# modicum.net
KiCad netlist of a schematic drawn in EAGLE
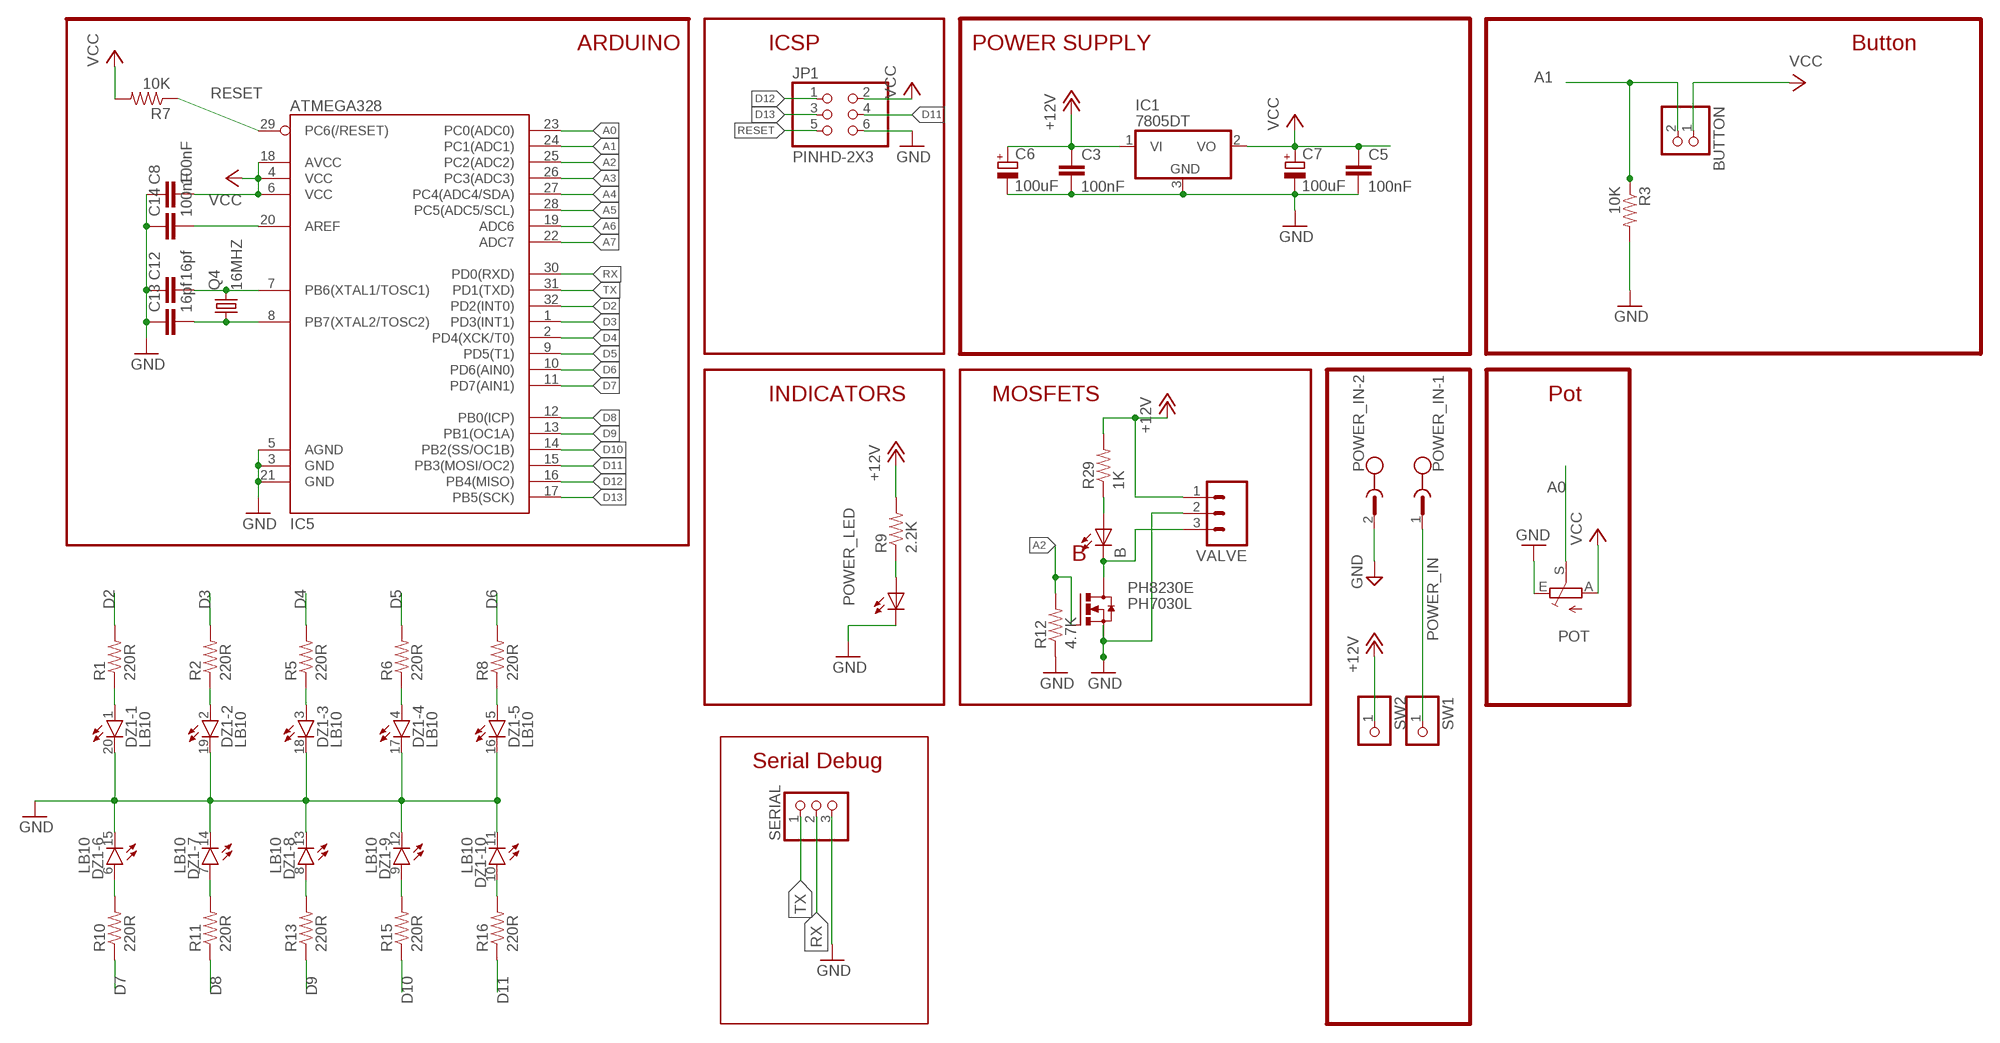
[diagram p0: schematic, sheet 1]

(export (version "E")
  (design (tool "Eeschema 10.0.6"))
  (components
    (comp (ref "B")
      (value "LED0805")
      (footprint "eagle-import:LED-0805")
      (libsource (lib "eagle-import") (part "LED0805"))
    )
    (comp (ref "BUTTON")
      (value "PINHD-1X2")
      (footprint "eagle-import:1X02")
      (libsource (lib "eagle-import") (part "PINHD-1X2"))
    )
    (comp (ref "C3")
      (value "100nF")
      (footprint "eagle-import:0805")
      (libsource (lib "eagle-import") (part "CAP0805"))
    )
    (comp (ref "C5")
      (value "100nF")
      (footprint "eagle-import:0805")
      (libsource (lib "eagle-import") (part "CAP0805"))
    )
    (comp (ref "C6")
      (value "100uF")
      (footprint "eagle-import:E3,5-8")
      (libsource (lib "eagle-import") (part "CPOL-EUE3.5-8"))
    )
    (comp (ref "C7")
      (value "100uF")
      (footprint "eagle-import:E3,5-8")
      (libsource (lib "eagle-import") (part "CPOL-EUE3.5-8"))
    )
    (comp (ref "C8")
      (value "100nF")
      (footprint "eagle-import:0805")
      (libsource (lib "eagle-import") (part "CAP0805"))
    )
    (comp (ref "C12")
      (value "16pf")
      (footprint "eagle-import:0805")
      (libsource (lib "eagle-import") (part "CAP0805"))
    )
    (comp (ref "C13")
      (value "16pf")
      (footprint "eagle-import:0805")
      (libsource (lib "eagle-import") (part "CAP0805"))
    )
    (comp (ref "C14")
      (value "100nF")
      (footprint "eagle-import:0805")
      (libsource (lib "eagle-import") (part "CAP0805"))
    )
    (comp (ref "DZ1")
      (value "LB10")
      (footprint "eagle-import:LB10")
      (libsource (lib "eagle-import") (part "LB10"))
    )
    (comp (ref "IC1")
      (value "7805DT")
      (footprint "eagle-import:TO252")
      (libsource (lib "eagle-import") (part "78DT05"))
    )
    (comp (ref "IC5")
      (value "ATMEGA328")
      (footprint "eagle-import:TQFP32-08")
      (libsource (lib "eagle-import") (part "ATMEGA168"))
    )
    (comp (ref "JP1")
      (value "PINHD-2X3")
      (footprint "eagle-import:2X03")
      (libsource (lib "eagle-import") (part "PINHD-2X3"))
    )
    (comp (ref "PH8230E")
      (value "PH7030L")
      (footprint "eagle-import:SOT669")
      (libsource (lib "eagle-import") (part "PH7030L"))
    )
    (comp (ref "POT")
      (value "TRIM_EU-CIP20C-6MM")
      (footprint "eagle-import:CIP20C-6MM")
      (libsource (lib "eagle-import") (part "TRIM_EU-CIP20C-6MM"))
    )
    (comp (ref "POWER_IN")
      (value "MST2V")
      (footprint "eagle-import:MSTBV2")
      (libsource (lib "eagle-import") (part "MST2V"))
    )
    (comp (ref "POWER_LED")
      (value "LED0805")
      (footprint "eagle-import:LED-0805")
      (libsource (lib "eagle-import") (part "LED0805"))
    )
    (comp (ref "Q4")
      (value "16MHZ")
      (footprint "eagle-import:HC49_S")
      (libsource (lib "eagle-import") (part "CRYSTALHC49S"))
    )
    (comp (ref "R1")
      (value "220R")
      (footprint "eagle-import:0805")
      (libsource (lib "eagle-import") (part "RESISTOR"))
    )
    (comp (ref "R2")
      (value "220R")
      (footprint "eagle-import:0805")
      (libsource (lib "eagle-import") (part "RESISTOR"))
    )
    (comp (ref "R3")
      (value "10K")
      (footprint "eagle-import:0805")
      (libsource (lib "eagle-import") (part "RESISTOR"))
    )
    (comp (ref "R5")
      (value "220R")
      (footprint "eagle-import:0805")
      (libsource (lib "eagle-import") (part "RESISTOR"))
    )
    (comp (ref "R6")
      (value "220R")
      (footprint "eagle-import:0805")
      (libsource (lib "eagle-import") (part "RESISTOR"))
    )
    (comp (ref "R7")
      (value "10K")
      (footprint "eagle-import:0805")
      (libsource (lib "eagle-import") (part "RESISTOR"))
    )
    (comp (ref "R8")
      (value "220R")
      (footprint "eagle-import:0805")
      (libsource (lib "eagle-import") (part "RESISTOR"))
    )
    (comp (ref "R9")
      (value "2.2K")
      (footprint "eagle-import:0805")
      (libsource (lib "eagle-import") (part "RESISTOR"))
    )
    (comp (ref "R10")
      (value "220R")
      (footprint "eagle-import:0805")
      (libsource (lib "eagle-import") (part "RESISTOR"))
    )
    (comp (ref "R11")
      (value "220R")
      (footprint "eagle-import:0805")
      (libsource (lib "eagle-import") (part "RESISTOR"))
    )
    (comp (ref "R12")
      (value "4.7K")
      (footprint "eagle-import:0805")
      (libsource (lib "eagle-import") (part "RESISTOR"))
    )
    (comp (ref "R13")
      (value "220R")
      (footprint "eagle-import:0805")
      (libsource (lib "eagle-import") (part "RESISTOR"))
    )
    (comp (ref "R15")
      (value "220R")
      (footprint "eagle-import:0805")
      (libsource (lib "eagle-import") (part "RESISTOR"))
    )
    (comp (ref "R16")
      (value "220R")
      (footprint "eagle-import:0805")
      (libsource (lib "eagle-import") (part "RESISTOR"))
    )
    (comp (ref "R29")
      (value "1K")
      (footprint "eagle-import:0805")
      (libsource (lib "eagle-import") (part "RESISTOR"))
    )
    (comp (ref "SERIAL")
      (value "PINHD-1X3")
      (footprint "eagle-import:1X03")
      (libsource (lib "eagle-import") (part "PINHD-1X3"))
    )
    (comp (ref "SW1")
      (value "PINHD-1X1")
      (footprint "eagle-import:1X01")
      (libsource (lib "eagle-import") (part "PINHD-1X1"))
    )
    (comp (ref "SW2")
      (value "PINHD-1X1")
      (footprint "eagle-import:1X01")
      (libsource (lib "eagle-import") (part "PINHD-1X1"))
    )
    (comp (ref "VALVE")
      (value "M03")
      (footprint "eagle-import:03P")
      (libsource (lib "eagle-import") (part "M03"))
    )
  )
  (nets
    (net (code "1") (name "+12V") (class "Default")
      (node (ref "C3") (pin "1") (pinfunction "1_1") (pintype "passive"))
      (node (ref "C6") (pin "+") (pinfunction "+_+") (pintype "passive"))
      (node (ref "IC1") (pin "1") (pinfunction "VI_1") (pintype "input"))
      (node (ref "R29") (pin "2") (pinfunction "2_2") (pintype "passive"))
      (node (ref "R9") (pin "2") (pinfunction "2_2") (pintype "passive"))
      (node (ref "SW2") (pin "1") (pinfunction "1_1") (pintype "passive"))
      (node (ref "VALVE") (pin "1") (pinfunction "1_1") (pintype "passive"))
    )
    (net (code "2") (name "/POWER_IN") (class "Default")
      (node (ref "POWER_IN") (pin "1") (pinfunction "1_1") (pintype "passive"))
      (node (ref "SW1") (pin "1") (pinfunction "1_1") (pintype "passive"))
    )
    (net (code "3") (name "A0") (class "Default")
      (node (ref "IC5") (pin "23") (pinfunction "PC0(ADC0)_23") (pintype "bidirectional"))
      (node (ref "POT") (pin "S") (pinfunction "S_S") (pintype "passive"))
    )
    (net (code "4") (name "A1") (class "Default")
      (node (ref "BUTTON") (pin "2") (pinfunction "2_2") (pintype "passive"))
      (node (ref "IC5") (pin "24") (pinfunction "PC1(ADC1)_24") (pintype "bidirectional"))
      (node (ref "R3") (pin "1") (pinfunction "1_1") (pintype "passive"))
    )
    (net (code "5") (name "A2") (class "Default")
      (node (ref "IC5") (pin "25") (pinfunction "PC2(ADC2)_25") (pintype "bidirectional"))
      (node (ref "PH8230E") (pin "4") (pinfunction "G_4") (pintype "passive"))
      (node (ref "R12") (pin "2") (pinfunction "2_2") (pintype "passive"))
    )
    (net (code "6") (name "A3") (class "Default")
      (node (ref "IC5") (pin "26") (pinfunction "PC3(ADC3)_26") (pintype "bidirectional"))
    )
    (net (code "7") (name "A4") (class "Default")
      (node (ref "IC5") (pin "27") (pinfunction "PC4(ADC4/SDA)_27") (pintype "bidirectional"))
    )
    (net (code "8") (name "A5") (class "Default")
      (node (ref "IC5") (pin "28") (pinfunction "PC5(ADC5/SCL)_28") (pintype "bidirectional"))
    )
    (net (code "9") (name "A6") (class "Default")
      (node (ref "IC5") (pin "19") (pinfunction "ADC6_19") (pintype "bidirectional"))
    )
    (net (code "10") (name "A7") (class "Default")
      (node (ref "IC5") (pin "22") (pinfunction "ADC7_22") (pintype "bidirectional"))
    )
    (net (code "11") (name "D2") (class "Default")
      (node (ref "IC5") (pin "32") (pinfunction "PD2(INT0)_32") (pintype "bidirectional"))
      (node (ref "R1") (pin "2") (pinfunction "2_2") (pintype "passive"))
    )
    (net (code "12") (name "D3") (class "Default")
      (node (ref "IC5") (pin "1") (pinfunction "PD3(INT1)_1") (pintype "bidirectional"))
      (node (ref "R2") (pin "2") (pinfunction "2_2") (pintype "passive"))
    )
    (net (code "13") (name "D4") (class "Default")
      (node (ref "IC5") (pin "2") (pinfunction "PD4(XCK/T0)_2") (pintype "bidirectional"))
      (node (ref "R5") (pin "2") (pinfunction "2_2") (pintype "passive"))
    )
    (net (code "14") (name "D5") (class "Default")
      (node (ref "IC5") (pin "9") (pinfunction "PD5(T1)_9") (pintype "bidirectional"))
      (node (ref "R6") (pin "2") (pinfunction "2_2") (pintype "passive"))
    )
    (net (code "15") (name "D6") (class "Default")
      (node (ref "IC5") (pin "10") (pinfunction "PD6(AIN0)_10") (pintype "bidirectional"))
      (node (ref "R8") (pin "2") (pinfunction "2_2") (pintype "passive"))
    )
    (net (code "16") (name "D7") (class "Default")
      (node (ref "IC5") (pin "11") (pinfunction "PD7(AIN1)_11") (pintype "bidirectional"))
      (node (ref "R10") (pin "1") (pinfunction "1_1") (pintype "passive"))
    )
    (net (code "17") (name "D8") (class "Default")
      (node (ref "IC5") (pin "12") (pinfunction "PB0(ICP)_12") (pintype "bidirectional"))
      (node (ref "R11") (pin "1") (pinfunction "1_1") (pintype "passive"))
    )
    (net (code "18") (name "D9") (class "Default")
      (node (ref "IC5") (pin "13") (pinfunction "PB1(OC1A)_13") (pintype "bidirectional"))
      (node (ref "R13") (pin "1") (pinfunction "1_1") (pintype "passive"))
    )
    (net (code "19") (name "D10") (class "Default")
      (node (ref "IC5") (pin "14") (pinfunction "PB2(SS/OC1B)_14") (pintype "bidirectional"))
      (node (ref "R15") (pin "1") (pinfunction "1_1") (pintype "passive"))
    )
    (net (code "20") (name "D11") (class "Default")
      (node (ref "IC5") (pin "15") (pinfunction "PB3(MOSI/OC2)_15") (pintype "bidirectional"))
      (node (ref "JP1") (pin "4") (pinfunction "4_4") (pintype "passive"))
      (node (ref "R16") (pin "1") (pinfunction "1_1") (pintype "passive"))
    )
    (net (code "21") (name "D12") (class "Default")
      (node (ref "IC5") (pin "16") (pinfunction "PB4(MISO)_16") (pintype "bidirectional"))
      (node (ref "JP1") (pin "1") (pinfunction "1_1") (pintype "passive"))
    )
    (net (code "22") (name "D13") (class "Default")
      (node (ref "IC5") (pin "17") (pinfunction "PB5(SCK)_17") (pintype "bidirectional"))
      (node (ref "JP1") (pin "3") (pinfunction "3_3") (pintype "passive"))
    )
    (net (code "23") (name "GND") (class "Default")
      (node (ref "C12") (pin "1") (pinfunction "1_1") (pintype "passive"))
      (node (ref "C13") (pin "1") (pinfunction "1_1") (pintype "passive"))
      (node (ref "C14") (pin "1") (pinfunction "1_1") (pintype "passive"))
      (node (ref "C3") (pin "2") (pinfunction "2_2") (pintype "passive"))
      (node (ref "C5") (pin "2") (pinfunction "2_2") (pintype "passive"))
      (node (ref "C6") (pin "-") (pinfunction "-_-") (pintype "passive"))
      (node (ref "C7") (pin "-") (pinfunction "-_-") (pintype "passive"))
      (node (ref "C8") (pin "1") (pinfunction "1_1") (pintype "passive"))
      (node (ref "DZ1") (pin "11") (pinfunction "C_11") (pintype "passive"))
      (node (ref "DZ1") (pin "12") (pinfunction "C_12") (pintype "passive"))
      (node (ref "DZ1") (pin "13") (pinfunction "C_13") (pintype "passive"))
      (node (ref "DZ1") (pin "14") (pinfunction "C_14") (pintype "passive"))
      (node (ref "DZ1") (pin "15") (pinfunction "C_15") (pintype "passive"))
      (node (ref "DZ1") (pin "16") (pinfunction "C_16") (pintype "passive"))
      (node (ref "DZ1") (pin "17") (pinfunction "C_17") (pintype "passive"))
      (node (ref "DZ1") (pin "18") (pinfunction "C_18") (pintype "passive"))
      (node (ref "DZ1") (pin "19") (pinfunction "C_19") (pintype "passive"))
      (node (ref "DZ1") (pin "20") (pinfunction "C_20") (pintype "passive"))
      (node (ref "IC1") (pin "3") (pinfunction "GND_3") (pintype "passive"))
      (node (ref "IC5") (pin "21") (pinfunction "GND_21") (pintype "bidirectional"))
      (node (ref "IC5") (pin "3") (pinfunction "GND_3") (pintype "bidirectional"))
      (node (ref "IC5") (pin "5") (pinfunction "AGND_5") (pintype "bidirectional"))
      (node (ref "JP1") (pin "6") (pinfunction "6_6") (pintype "passive"))
      (node (ref "PH8230E") (pin "1") (pinfunction "S_1") (pintype "passive"))
      (node (ref "PH8230E") (pin "2") (pinfunction "S_2") (pintype "passive"))
      (node (ref "PH8230E") (pin "3") (pinfunction "S_3") (pintype "passive"))
      (node (ref "POT") (pin "E") (pinfunction "E_E") (pintype "passive"))
      (node (ref "POWER_IN") (pin "2") (pinfunction "1_2") (pintype "passive"))
      (node (ref "POWER_LED") (pin "C") (pinfunction "C_C") (pintype "passive"))
      (node (ref "R12") (pin "1") (pinfunction "1_1") (pintype "passive"))
      (node (ref "R3") (pin "2") (pinfunction "2_2") (pintype "passive"))
      (node (ref "SERIAL") (pin "3") (pinfunction "3_3") (pintype "passive"))
      (node (ref "VALVE") (pin "2") (pinfunction "2_2") (pintype "passive"))
    )
    (net (code "24") (name "Net-(B-PadA)") (class "Default")
      (node (ref "B") (pin "A") (pinfunction "A_A") (pintype "passive"))
      (node (ref "R29") (pin "1") (pinfunction "1_1") (pintype "passive"))
    )
    (net (code "25") (name "Net-(DZ1A-A)") (class "Default")
      (node (ref "DZ1") (pin "1") (pinfunction "A_1") (pintype "passive"))
      (node (ref "R1") (pin "1") (pinfunction "1_1") (pintype "passive"))
    )
    (net (code "26") (name "Net-(DZ1B-A)") (class "Default")
      (node (ref "DZ1") (pin "10") (pinfunction "A_10") (pintype "passive"))
      (node (ref "R16") (pin "2") (pinfunction "2_2") (pintype "passive"))
    )
    (net (code "27") (name "Net-(DZ1C-A)") (class "Default")
      (node (ref "DZ1") (pin "2") (pinfunction "A_2") (pintype "passive"))
      (node (ref "R2") (pin "1") (pinfunction "1_1") (pintype "passive"))
    )
    (net (code "28") (name "Net-(DZ1D-A)") (class "Default")
      (node (ref "DZ1") (pin "3") (pinfunction "A_3") (pintype "passive"))
      (node (ref "R5") (pin "1") (pinfunction "1_1") (pintype "passive"))
    )
    (net (code "29") (name "Net-(DZ1E-A)") (class "Default")
      (node (ref "DZ1") (pin "4") (pinfunction "A_4") (pintype "passive"))
      (node (ref "R6") (pin "1") (pinfunction "1_1") (pintype "passive"))
    )
    (net (code "30") (name "Net-(DZ1F-A)") (class "Default")
      (node (ref "DZ1") (pin "5") (pinfunction "A_5") (pintype "passive"))
      (node (ref "R8") (pin "1") (pinfunction "1_1") (pintype "passive"))
    )
    (net (code "31") (name "Net-(DZ1G-A)") (class "Default")
      (node (ref "DZ1") (pin "6") (pinfunction "A_6") (pintype "passive"))
      (node (ref "R10") (pin "2") (pinfunction "2_2") (pintype "passive"))
    )
    (net (code "32") (name "Net-(DZ1H-A)") (class "Default")
      (node (ref "DZ1") (pin "7") (pinfunction "A_7") (pintype "passive"))
      (node (ref "R11") (pin "2") (pinfunction "2_2") (pintype "passive"))
    )
    (net (code "33") (name "Net-(DZ1I-A)") (class "Default")
      (node (ref "DZ1") (pin "8") (pinfunction "A_8") (pintype "passive"))
      (node (ref "R13") (pin "2") (pinfunction "2_2") (pintype "passive"))
    )
    (net (code "34") (name "Net-(DZ1J-A)") (class "Default")
      (node (ref "DZ1") (pin "9") (pinfunction "A_9") (pintype "passive"))
      (node (ref "R15") (pin "2") (pinfunction "2_2") (pintype "passive"))
    )
    (net (code "35") (name "Net-(IC5-AREF)") (class "Default")
      (node (ref "C14") (pin "2") (pinfunction "2_2") (pintype "passive"))
      (node (ref "IC5") (pin "20") (pinfunction "AREF_20") (pintype "bidirectional"))
    )
    (net (code "36") (name "Net-(IC5-PB6(XTAL1{slash}TOSC1))") (class "Default")
      (node (ref "C12") (pin "2") (pinfunction "2_2") (pintype "passive"))
      (node (ref "IC5") (pin "7") (pinfunction "PB6(XTAL1/TOSC1)_7") (pintype "bidirectional"))
      (node (ref "Q4") (pin "2") (pinfunction "2_2") (pintype "passive"))
    )
    (net (code "37") (name "Net-(IC5-PB7(XTAL2{slash}TOSC2))") (class "Default")
      (node (ref "C13") (pin "2") (pinfunction "2_2") (pintype "passive"))
      (node (ref "IC5") (pin "8") (pinfunction "PB7(XTAL2/TOSC2)_8") (pintype "bidirectional"))
      (node (ref "Q4") (pin "1") (pinfunction "1_1") (pintype "passive"))
    )
    (net (code "38") (name "Net-(PH8230E-D)") (class "Default")
      (node (ref "B") (pin "C") (pinfunction "C_C") (pintype "passive"))
      (node (ref "PH8230E") (pin "MB") (pinfunction "D_MB") (pintype "passive"))
      (node (ref "VALVE") (pin "3") (pinfunction "3_3") (pintype "passive"))
    )
    (net (code "39") (name "Net-(POWER_LED-PadA)") (class "Default")
      (node (ref "POWER_LED") (pin "A") (pinfunction "A_A") (pintype "passive"))
      (node (ref "R9") (pin "1") (pinfunction "1_1") (pintype "passive"))
    )
    (net (code "40") (name "RESET") (class "Default")
      (node (ref "IC5") (pin "29") (pinfunction "PC6(/RESET)_29") (pintype "bidirectional"))
      (node (ref "JP1") (pin "5") (pinfunction "5_5") (pintype "passive"))
      (node (ref "R7") (pin "1") (pinfunction "1_1") (pintype "passive"))
    )
    (net (code "41") (name "RX") (class "Default")
      (node (ref "IC5") (pin "30") (pinfunction "PD0(RXD)_30") (pintype "bidirectional"))
      (node (ref "SERIAL") (pin "2") (pinfunction "2_2") (pintype "passive"))
    )
    (net (code "42") (name "TX") (class "Default")
      (node (ref "IC5") (pin "31") (pinfunction "PD1(TXD)_31") (pintype "bidirectional"))
      (node (ref "SERIAL") (pin "1") (pinfunction "1_1") (pintype "passive"))
    )
    (net (code "43") (name "VCC") (class "Default")
      (node (ref "BUTTON") (pin "1") (pinfunction "1_1") (pintype "passive"))
      (node (ref "C5") (pin "1") (pinfunction "1_1") (pintype "passive"))
      (node (ref "C7") (pin "+") (pinfunction "+_+") (pintype "passive"))
      (node (ref "C8") (pin "2") (pinfunction "2_2") (pintype "passive"))
      (node (ref "IC1") (pin "2") (pinfunction "VO_2") (pintype "passive"))
      (node (ref "IC5") (pin "18") (pinfunction "AVCC_18") (pintype "bidirectional"))
      (node (ref "IC5") (pin "4") (pinfunction "VCC_4") (pintype "bidirectional"))
      (node (ref "IC5") (pin "6") (pinfunction "VCC_6") (pintype "bidirectional"))
      (node (ref "JP1") (pin "2") (pinfunction "2_2") (pintype "passive"))
      (node (ref "POT") (pin "A") (pinfunction "A_A") (pintype "passive"))
      (node (ref "R7") (pin "2") (pinfunction "2_2") (pintype "passive"))
    )
  )
)
